# SFP_uptoSFP28.net
KiCad netlist of a schematic drawn in Altium Designer
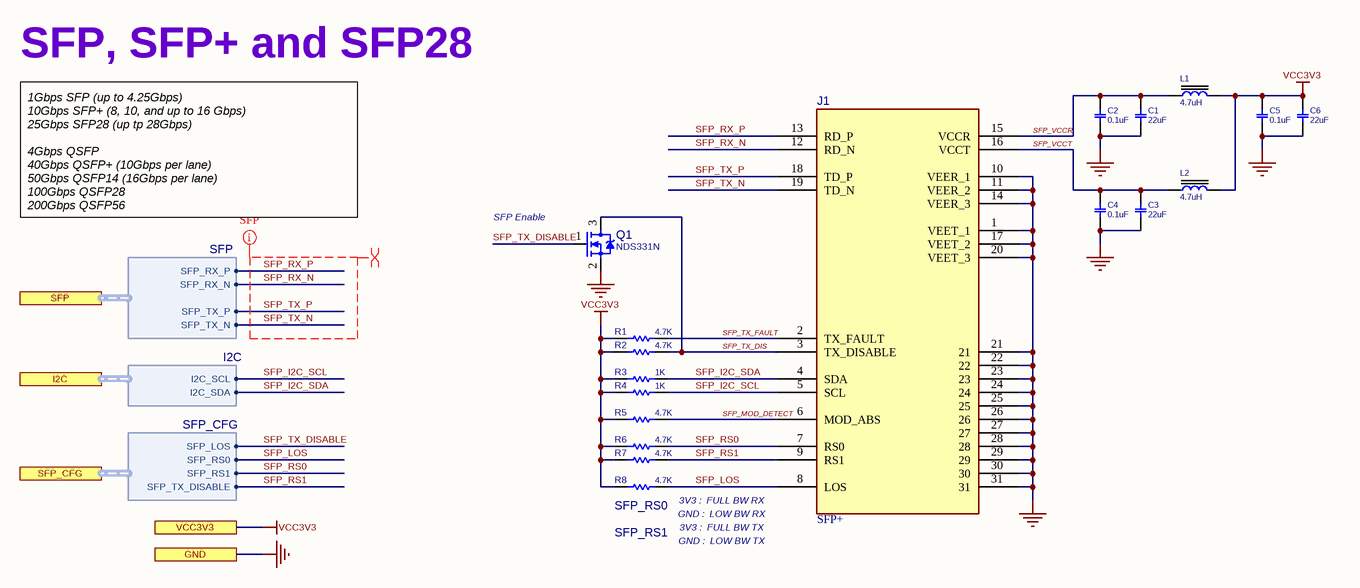
[diagram p0: SFP_uptoSFP28.SchDoc]

(export (version "E")
  (design (tool "Eeschema 10.0.6"))
  (components
    (comp (ref "C1")
      (value "22uF")
      (footprint "C0603")
      (description "CAP, MLCC, X5R 22uF 20% 25V")
      (fields (field (name "MANF_P#") "JMK325BJ107MM-T") (field (name "MANF") "Taiyo Yuden"))
      (libsource (lib "mlcc_smd_passive") (part "CAP_SMD_MLCC_100u6.3VT"))
    )
    (comp (ref "C2")
      (value "0.1uF")
      (footprint "C0402")
      (description "CAP, MLCC, 100nF, 50V, X7R, 10%, 0402C")
      (fields (field (name "MANF") "Taiyo Yuden") (field (name "MANF_P#") "UMK105B7104KVHF"))
      (libsource (lib "mlcc_smd_passive") (part "CAP_SMD_MLCC_100n50T"))
    )
    (comp (ref "C3")
      (value "22uF")
      (footprint "C0603")
      (description "CAP, MLCC, X5R 22uF 20% 25V")
      (fields (field (name "MANF_P#") "JMK325BJ107MM-T") (field (name "MANF") "Taiyo Yuden"))
      (libsource (lib "mlcc_smd_passive") (part "CAP_SMD_MLCC_100u6.3VT"))
    )
    (comp (ref "C4")
      (value "0.1uF")
      (footprint "C0402")
      (description "CAP, MLCC, 100nF, 50V, X7R, 10%, 0402C")
      (fields (field (name "MANF") "Taiyo Yuden") (field (name "MANF_P#") "UMK105B7104KVHF"))
      (libsource (lib "mlcc_smd_passive") (part "CAP_SMD_MLCC_100n50T"))
    )
    (comp (ref "C5")
      (value "0.1uF")
      (footprint "C0402")
      (description "CAP, MLCC, 100nF, 50V, X7R, 10%, 0402C")
      (fields (field (name "MANF") "Taiyo Yuden") (field (name "MANF_P#") "UMK105B7104KVHF"))
      (libsource (lib "mlcc_smd_passive") (part "CAP_SMD_MLCC_100n50T"))
    )
    (comp (ref "C6")
      (value "22uF")
      (footprint "C0603")
      (description "CAP, MLCC, X5R 22uF 20% 25V")
      (fields (field (name "MANF_P#") "JMK325BJ107MM-T") (field (name "MANF") "Taiyo Yuden"))
      (libsource (lib "mlcc_smd_passive") (part "CAP_SMD_MLCC_100u6.3VT"))
    )
    (comp (ref "J1")
      (value "SFP+")
      (footprint "SFP_20_SH")
      (description "CONN, SFP PLUS (SFP+) RCPT 20POS R/A GOLD SMD")
      (fields (field (name "MANF") "Molex") (field (name "MANF_P#") "74441-0010"))
      (libsource (lib "conn_optic") (part "CONN_SFP_20_SH"))
    )
    (comp (ref "L1")
      (value "4.7uH")
      (footprint "L_3")
      (description "INDUCTOR")
      (fields (field (name "MANF_P#") "XAL4020-102MEC") (field (name "MANF") "Coilcraft"))
      (libsource (lib "inductor_power") (part "IND_SMD_2.2uH_2.9A"))
    )
    (comp (ref "L2")
      (value "4.7uH")
      (footprint "L_3")
      (description "INDUCTOR")
      (fields (field (name "MANF_P#") "XAL4020-102MEC") (field (name "MANF") "Coilcraft"))
      (libsource (lib "inductor_power") (part "IND_SMD_2.2uH_2.9A"))
    )
    (comp (ref "Q1")
      (value "NDS331N")
      (footprint "SOT23_3")
      (description "MOSFET N-CH 20V 1.3A 3-SSOT")
      (fields (field (name "MANF") "Fairchild"))
      (libsource (lib "transistor_fet") (part "MOSN_NDS331N_SOT23"))
    )
    (comp (ref "R1")
      (value "4.7K")
      (footprint "R0402")
      (description "RESISTOR, SMD")
      (fields (field (name "MANF") "Yageo") (field (name "MANF_P#") "RC0402FR-074K7L"))
      (libsource (lib "passive_res_smd") (part "RES_SMD_10K_0402"))
    )
    (comp (ref "R2")
      (value "4.7K")
      (footprint "R0402")
      (description "RESISTOR, SMD")
      (fields (field (name "MANF") "Yageo") (field (name "MANF_P#") "RC0402FR-074K7L"))
      (libsource (lib "passive_res_smd") (part "RES_SMD_10K_0402"))
    )
    (comp (ref "R3")
      (value "1K")
      (footprint "R0402")
      (description "RESISTOR, SMD")
      (fields (field (name "MANF_P#") "RK73Z1ETTP") (field (name "MANF") "KOA SPEER"))
      (libsource (lib "res_smd_KoaSpeer0402") (part "RES_SMD_0_0402"))
    )
    (comp (ref "R4")
      (value "1K")
      (footprint "R0402")
      (description "RESISTOR, SMD")
      (fields (field (name "MANF_P#") "RK73Z1ETTP") (field (name "MANF") "KOA SPEER"))
      (libsource (lib "res_smd_KoaSpeer0402") (part "RES_SMD_0_0402"))
    )
    (comp (ref "R5")
      (value "4.7K")
      (footprint "R0402")
      (description "RESISTOR, SMD")
      (fields (field (name "MANF") "Yageo") (field (name "MANF_P#") "RC0402FR-074K7L"))
      (libsource (lib "passive_res_smd") (part "RES_SMD_10K_0402"))
    )
    (comp (ref "R6")
      (value "4.7K")
      (footprint "R0402")
      (description "RESISTOR, SMD")
      (fields (field (name "MANF") "Yageo") (field (name "MANF_P#") "RC0402FR-074K7L"))
      (libsource (lib "passive_res_smd") (part "RES_SMD_10K_0402"))
    )
    (comp (ref "R7")
      (value "4.7K")
      (footprint "R0402")
      (description "RESISTOR, SMD")
      (fields (field (name "MANF") "Yageo") (field (name "MANF_P#") "RC0402FR-074K7L"))
      (libsource (lib "passive_res_smd") (part "RES_SMD_10K_0402"))
    )
    (comp (ref "R8")
      (value "4.7K")
      (footprint "R0402")
      (description "RESISTOR, SMD")
      (fields (field (name "MANF") "Yageo") (field (name "MANF_P#") "RC0402FR-074K7L"))
      (libsource (lib "passive_res_smd") (part "RES_SMD_10K_0402"))
    )
  )
  (nets
    (net (code "4") (name "/SFP_I2C_SCL") (class "Default")
      (node (ref "J1") (pin "5") (pinfunction "SCL_5") (pintype "passive"))
      (node (ref "R4") (pin "2") (pinfunction "2_2") (pintype "passive"))
    )
    (net (code "5") (name "/SFP_I2C_SDA") (class "Default")
      (node (ref "J1") (pin "4") (pinfunction "SDA_4") (pintype "passive"))
      (node (ref "R3") (pin "2") (pinfunction "2_2") (pintype "passive"))
    )
    (net (code "6") (name "/SFP_LOS") (class "Default")
      (node (ref "J1") (pin "8") (pinfunction "LOS_8") (pintype "passive"))
      (node (ref "R8") (pin "1") (pinfunction "1_1") (pintype "passive"))
    )
    (net (code "7") (name "/SFP_MOD_DETECT") (class "Default")
      (node (ref "J1") (pin "6") (pinfunction "MOD_ABS_6") (pintype "passive"))
      (node (ref "R5") (pin "1") (pinfunction "1_1") (pintype "passive"))
    )
    (net (code "8") (name "/SFP_RS0") (class "Default")
      (node (ref "J1") (pin "7") (pinfunction "RS0_7") (pintype "passive"))
      (node (ref "R6") (pin "1") (pinfunction "1_1") (pintype "passive"))
    )
    (net (code "9") (name "/SFP_RS1") (class "Default")
      (node (ref "J1") (pin "9") (pinfunction "RS1_9") (pintype "passive"))
      (node (ref "R7") (pin "1") (pinfunction "1_1") (pintype "passive"))
    )
    (net (code "10") (name "/SFP_RX_N") (class "Default")
      (node (ref "J1") (pin "12") (pinfunction "RD_N_12") (pintype "passive"))
    )
    (net (code "11") (name "/SFP_RX_P") (class "Default")
      (node (ref "J1") (pin "13") (pinfunction "RD_P_13") (pintype "passive"))
    )
    (net (code "12") (name "/SFP_TX_DIS") (class "Default")
      (node (ref "J1") (pin "3") (pinfunction "TX_DISABLE_3") (pintype "passive"))
      (node (ref "Q1") (pin "3") (pinfunction "DRAIN_3") (pintype "passive"))
      (node (ref "R2") (pin "1") (pinfunction "1_1") (pintype "passive"))
    )
    (net (code "13") (name "/SFP_TX_DISABLE") (class "Default")
      (node (ref "Q1") (pin "1") (pinfunction "GATE_1") (pintype "passive"))
    )
    (net (code "14") (name "/SFP_TX_FAULT") (class "Default")
      (node (ref "J1") (pin "2") (pinfunction "TX_FAULT_2") (pintype "passive"))
      (node (ref "R1") (pin "1") (pinfunction "1_1") (pintype "passive"))
    )
    (net (code "15") (name "/SFP_TX_N") (class "Default")
      (node (ref "J1") (pin "19") (pinfunction "TD_N_19") (pintype "passive"))
    )
    (net (code "16") (name "/SFP_TX_P") (class "Default")
      (node (ref "J1") (pin "18") (pinfunction "TD_P_18") (pintype "passive"))
    )
    (net (code "17") (name "/SFP_VCCR") (class "Default")
      (node (ref "C1") (pin "1") (pinfunction "1_1") (pintype "passive"))
      (node (ref "C2") (pin "1") (pinfunction "1_1") (pintype "passive"))
      (node (ref "J1") (pin "15") (pinfunction "VCCR_15") (pintype "passive"))
      (node (ref "L1") (pin "1") (pinfunction "1_1") (pintype "passive"))
    )
    (net (code "18") (name "/SFP_VCCT") (class "Default")
      (node (ref "C3") (pin "1") (pinfunction "1_1") (pintype "passive"))
      (node (ref "C4") (pin "2") (pinfunction "2_2") (pintype "passive"))
      (node (ref "J1") (pin "16") (pinfunction "VCCT_16") (pintype "passive"))
      (node (ref "L2") (pin "1") (pinfunction "1_1") (pintype "passive"))
    )
    (net (code "22") (name "GND") (class "Default")
      (node (ref "C1") (pin "2") (pinfunction "2_2") (pintype "passive"))
      (node (ref "C2") (pin "2") (pinfunction "2_2") (pintype "passive"))
      (node (ref "C3") (pin "2") (pinfunction "2_2") (pintype "passive"))
      (node (ref "C4") (pin "1") (pinfunction "1_1") (pintype "passive"))
      (node (ref "C5") (pin "1") (pinfunction "1_1") (pintype "passive"))
      (node (ref "C6") (pin "2") (pinfunction "2_2") (pintype "passive"))
      (node (ref "J1") (pin "1") (pinfunction "VEET_1_1") (pintype "passive"))
      (node (ref "J1") (pin "10") (pinfunction "VEER_1_10") (pintype "passive"))
      (node (ref "J1") (pin "11") (pinfunction "VEER_2_11") (pintype "passive"))
      (node (ref "J1") (pin "14") (pinfunction "VEER_3_14") (pintype "passive"))
      (node (ref "J1") (pin "17") (pinfunction "VEET_2_17") (pintype "passive"))
      (node (ref "J1") (pin "20") (pinfunction "VEET_3_20") (pintype "passive"))
      (node (ref "J1") (pin "21") (pinfunction "21_21") (pintype "passive"))
      (node (ref "J1") (pin "22") (pinfunction "22_22") (pintype "passive"))
      (node (ref "J1") (pin "23") (pinfunction "23_23") (pintype "passive"))
      (node (ref "J1") (pin "24") (pinfunction "24_24") (pintype "passive"))
      (node (ref "J1") (pin "25") (pinfunction "25_25") (pintype "passive"))
      (node (ref "J1") (pin "26") (pinfunction "26_26") (pintype "passive"))
      (node (ref "J1") (pin "27") (pinfunction "27_27") (pintype "passive"))
      (node (ref "J1") (pin "28") (pinfunction "28_28") (pintype "passive"))
      (node (ref "J1") (pin "29") (pinfunction "29_29") (pintype "passive"))
      (node (ref "J1") (pin "30") (pinfunction "30_30") (pintype "passive"))
      (node (ref "J1") (pin "31") (pinfunction "31_31") (pintype "passive"))
      (node (ref "Q1") (pin "2") (pinfunction "SOURCE_2") (pintype "passive"))
    )
    (net (code "23") (name "VCC3V3") (class "Default")
      (node (ref "C5") (pin "2") (pinfunction "2_2") (pintype "passive"))
      (node (ref "C6") (pin "1") (pinfunction "1_1") (pintype "passive"))
      (node (ref "L1") (pin "2") (pinfunction "2_2") (pintype "passive"))
      (node (ref "L2") (pin "2") (pinfunction "2_2") (pintype "passive"))
      (node (ref "R1") (pin "2") (pinfunction "2_2") (pintype "passive"))
      (node (ref "R2") (pin "2") (pinfunction "2_2") (pintype "passive"))
      (node (ref "R3") (pin "1") (pinfunction "1_1") (pintype "passive"))
      (node (ref "R4") (pin "1") (pinfunction "1_1") (pintype "passive"))
      (node (ref "R5") (pin "2") (pinfunction "2_2") (pintype "passive"))
      (node (ref "R6") (pin "2") (pinfunction "2_2") (pintype "passive"))
      (node (ref "R7") (pin "2") (pinfunction "2_2") (pintype "passive"))
      (node (ref "R8") (pin "2") (pinfunction "2_2") (pintype "passive"))
    )
  )
)
